# czujniki.net
KiCad netlist of a schematic drawn in EAGLE
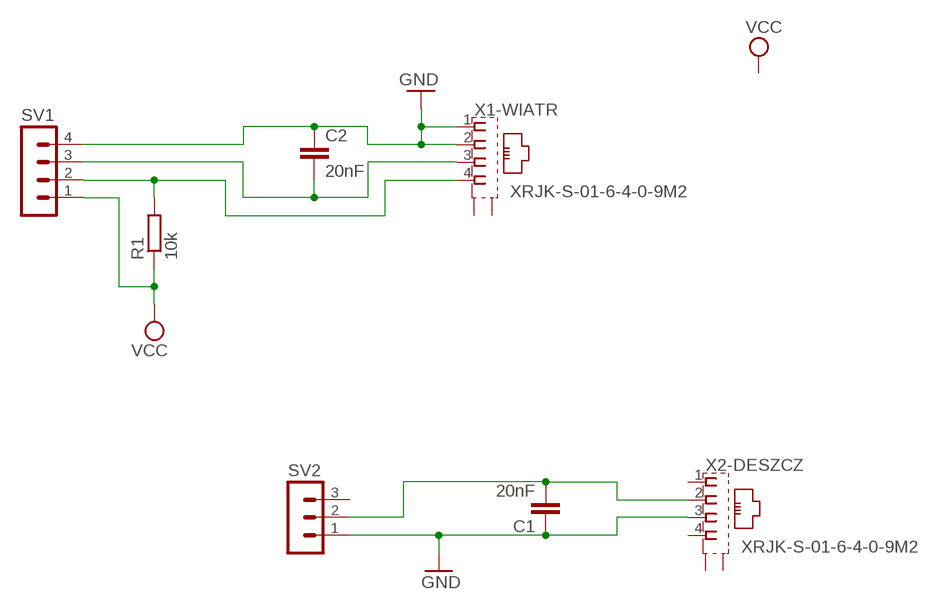
[diagram p0: schematic, sheet 1]

(export (version "E")
  (design (tool "Eeschema 10.0.6"))
  (components
    (comp (ref "C1")
      (value "20nF")
      (footprint "eagle-import:C2.5-2")
      (libsource (lib "eagle-import") (part "C2.5/2"))
    )
    (comp (ref "C2")
      (value "20nF")
      (footprint "eagle-import:C2.5-2")
      (libsource (lib "eagle-import") (part "C2.5/2"))
    )
    (comp (ref "R1")
      (value "10k")
      (footprint "eagle-import:M1206")
      (libsource (lib "eagle-import") (part "R-EU_M1206"))
    )
    (comp (ref "SV1")
      (value "MA04-1")
      (footprint "eagle-import:MA04-1")
      (libsource (lib "eagle-import") (part "MA04-1"))
    )
    (comp (ref "SV2")
      (value "MA03-1")
      (footprint "eagle-import:MA03-1")
      (libsource (lib "eagle-import") (part "MA03-1"))
    )
    (comp (ref "X1-WIATR")
      (value "XRJK-S-01-6-4-0-9M2")
      (footprint "eagle-import:XRJK-S-01-6-4-0-9M2")
      (libsource (lib "eagle-import") (part "XRJK4-0-9M2-S-01-6-"))
    )
    (comp (ref "X2-DESZCZ")
      (value "XRJK-S-01-6-4-0-9M2")
      (footprint "eagle-import:XRJK-S-01-6-4-0-9M2")
      (libsource (lib "eagle-import") (part "XRJK4-0-9M2-S-01-6-"))
    )
  )
  (nets
    (net (code "1") (name "GND") (class "Default")
      (node (ref "C1") (pin "1") (pinfunction "1_1") (pintype "passive"))
      (node (ref "C2") (pin "1") (pinfunction "1_1") (pintype "passive"))
      (node (ref "SV1") (pin "4") (pinfunction "4_4") (pintype "passive"))
      (node (ref "SV2") (pin "1") (pinfunction "1_1") (pintype "passive"))
      (node (ref "X1-WIATR") (pin "1") (pinfunction "1_1") (pintype "passive"))
      (node (ref "X1-WIATR") (pin "2") (pinfunction "2_2") (pintype "passive"))
      (node (ref "X2-DESZCZ") (pin "3") (pinfunction "3_3") (pintype "passive"))
    )
    (net (code "2") (name "Net-(C1-Pad2)") (class "Default")
      (node (ref "C1") (pin "2") (pinfunction "2_2") (pintype "passive"))
      (node (ref "SV2") (pin "2") (pinfunction "2_2") (pintype "passive"))
      (node (ref "X2-DESZCZ") (pin "2") (pinfunction "2_2") (pintype "passive"))
    )
    (net (code "3") (name "Net-(C2-Pad2)") (class "Default")
      (node (ref "C2") (pin "2") (pinfunction "2_2") (pintype "passive"))
      (node (ref "SV1") (pin "3") (pinfunction "3_3") (pintype "passive"))
      (node (ref "X1-WIATR") (pin "3") (pinfunction "3_3") (pintype "passive"))
    )
    (net (code "4") (name "Net-(R1-Pad2)") (class "Default")
      (node (ref "R1") (pin "2") (pinfunction "2_2") (pintype "passive"))
      (node (ref "SV1") (pin "2") (pinfunction "2_2") (pintype "passive"))
      (node (ref "X1-WIATR") (pin "4") (pinfunction "4_4") (pintype "passive"))
    )
    (net (code "5") (name "VCC") (class "Default")
      (node (ref "R1") (pin "1") (pinfunction "1_1") (pintype "passive"))
      (node (ref "SV1") (pin "1") (pinfunction "1_1") (pintype "passive"))
    )
    (net (code "6") (name "unconnected-(SV2-Pad3)") (class "Default")
      (node (ref "SV2") (pin "3") (pinfunction "3_3") (pintype "passive"))
    )
    (net (code "7") (name "unconnected-(X1-WIATR-S-PadS1)") (class "Default")
      (node (ref "X1-WIATR") (pin "S1") (pinfunction "S_S1") (pintype "passive"))
    )
    (net (code "8") (name "unconnected-(X1-WIATR-S-PadS2)") (class "Default")
      (node (ref "X1-WIATR") (pin "S2") (pinfunction "S_S2") (pintype "passive"))
    )
    (net (code "9") (name "unconnected-(X2-DESZCZ-Pad1)") (class "Default")
      (node (ref "X2-DESZCZ") (pin "1") (pinfunction "1_1") (pintype "passive"))
    )
    (net (code "10") (name "unconnected-(X2-DESZCZ-Pad4)") (class "Default")
      (node (ref "X2-DESZCZ") (pin "4") (pinfunction "4_4") (pintype "passive"))
    )
    (net (code "11") (name "unconnected-(X2-DESZCZ-S-PadS1)") (class "Default")
      (node (ref "X2-DESZCZ") (pin "S1") (pinfunction "S_S1") (pintype "passive"))
    )
    (net (code "12") (name "unconnected-(X2-DESZCZ-S-PadS2)") (class "Default")
      (node (ref "X2-DESZCZ") (pin "S2") (pinfunction "S_S2") (pintype "passive"))
    )
  )
)
